# ADC.net
KiCad netlist of a schematic drawn in Altium Designer
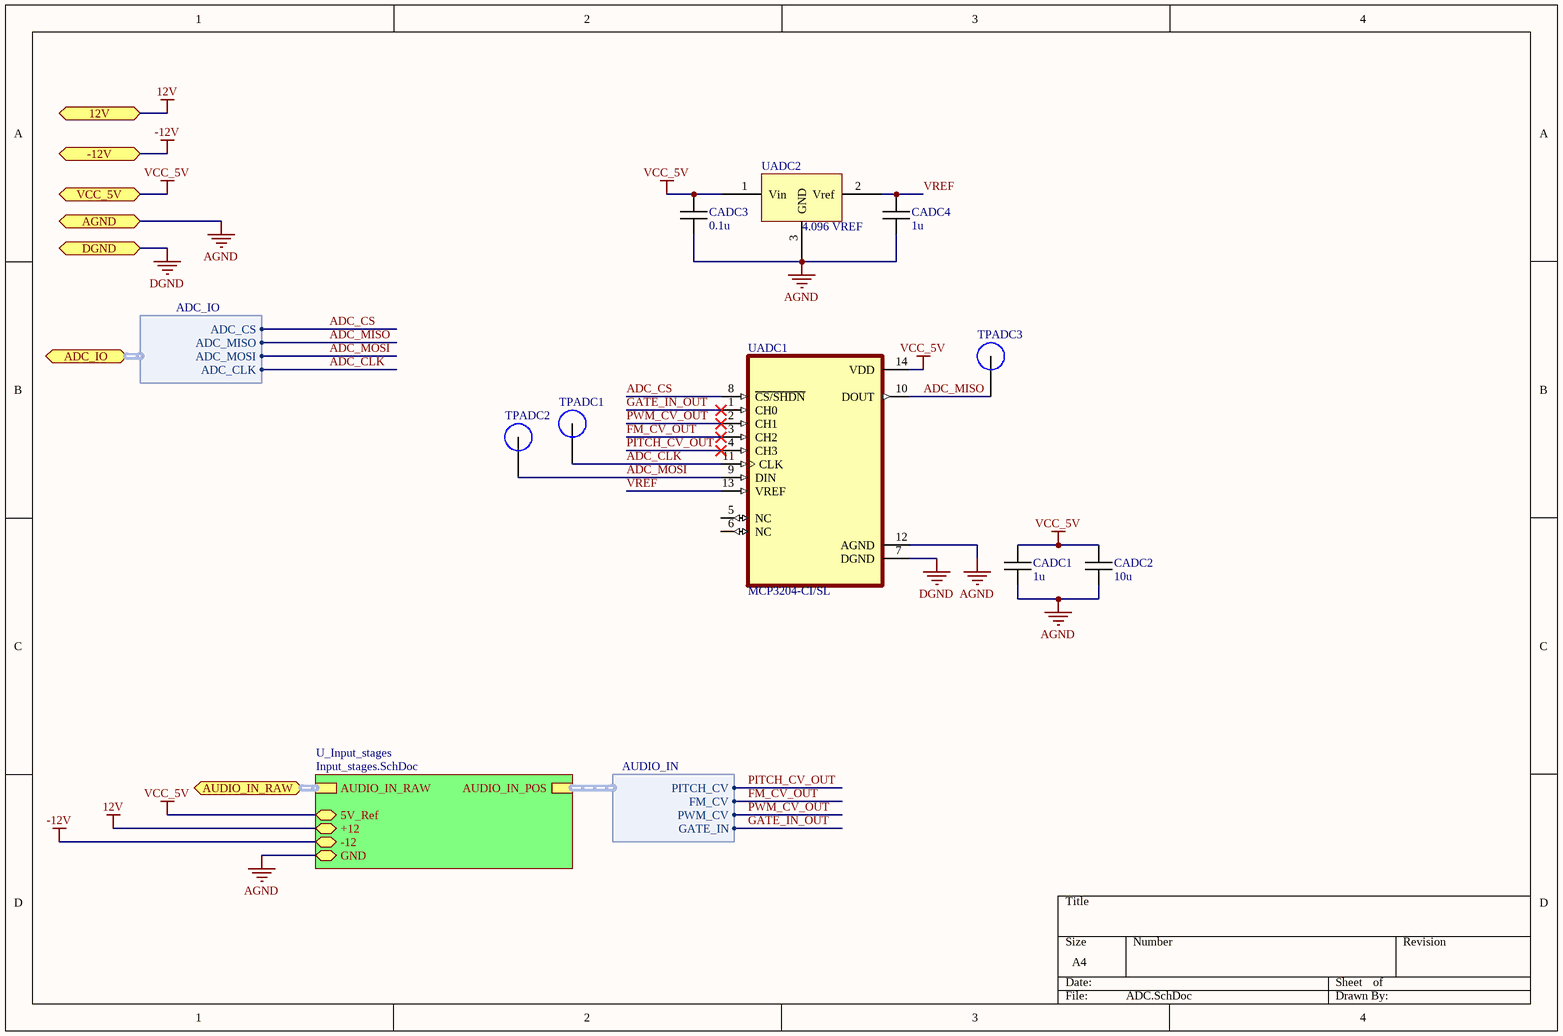
[diagram p0: ADC.SchDoc]

(export (version "E")
  (design (tool "Eeschema 10.0.6"))
  (components
    (comp (ref "CADC1")
      (value "1u")
      (footprint "C 0603 / 1608")
      (libsource (lib "Standard") (part "Capacitor"))
    )
    (comp (ref "CADC2")
      (value "10u")
      (footprint "C 0603 / 1608")
      (libsource (lib "Standard") (part "Capacitor"))
    )
    (comp (ref "CADC3")
      (value "0.1u")
      (footprint "C 0603 / 1608")
      (libsource (lib "Standard") (part "Capacitor"))
    )
    (comp (ref "CADC4")
      (value "1u")
      (footprint "C 0603 / 1608")
      (libsource (lib "Standard") (part "Capacitor"))
    )
    (comp (ref "TPADC1")
      (value "Test Point")
      (footprint "Test POint")
      (libsource (lib "Standard") (part "Test Point"))
    )
    (comp (ref "TPADC2")
      (value "Test Point")
      (footprint "Test POint")
      (libsource (lib "Standard") (part "Test Point"))
    )
    (comp (ref "TPADC3")
      (value "Test Point")
      (footprint "Test POint")
      (libsource (lib "Standard") (part "Test Point"))
    )
    (comp (ref "UADC1")
      (value "MCP3204-CI/SL")
      (footprint "SOIC-14")
      (description "12 Bit Analog to Digital Converter 2, 4 Input 1 SAR 14-SOIC")
      (fields (field (name "MF") "Microchip"))
      (libsource (lib "IC") (part "MCP3204-CI/SL"))
    )
    (comp (ref "UADC2")
      (value "4.096 VREF")
      (footprint "SOT-23-3")
      (description "4.096 Voltage reference")
      (libsource (lib "IC") (part "MCP1541"))
    )
  )
  (nets
    (net (code "5") (name "/ADC_CLK") (class "Default")
      (node (ref "TPADC1") (pin "1") (pintype "passive"))
      (node (ref "UADC1") (pin "11") (pinfunction "CLK_11") (pintype "input"))
    )
    (net (code "6") (name "/ADC_CS") (class "Default")
      (node (ref "UADC1") (pin "8") (pinfunction "~{CS/SHDN}_8") (pintype "input"))
    )
    (net (code "7") (name "/ADC_MISO") (class "Default")
      (node (ref "TPADC3") (pin "1") (pintype "passive"))
      (node (ref "UADC1") (pin "10") (pinfunction "DOUT_10") (pintype "output"))
    )
    (net (code "8") (name "/ADC_MOSI") (class "Default")
      (node (ref "TPADC2") (pin "1") (pintype "passive"))
      (node (ref "UADC1") (pin "9") (pinfunction "DIN_9") (pintype "input"))
    )
    (net (code "10") (name "/FM_CV_OUT") (class "Default")
      (node (ref "UADC1") (pin "3") (pinfunction "CH2_3") (pintype "input"))
    )
    (net (code "11") (name "/GATE_IN_OUT") (class "Default")
      (node (ref "UADC1") (pin "1") (pinfunction "CH0_1") (pintype "input"))
    )
    (net (code "12") (name "/PITCH_CV_OUT") (class "Default")
      (node (ref "UADC1") (pin "4") (pinfunction "CH3_4") (pintype "input"))
    )
    (net (code "13") (name "/PWM_CV_OUT") (class "Default")
      (node (ref "UADC1") (pin "2") (pinfunction "CH1_2") (pintype "input"))
    )
    (net (code "14") (name "/VREF") (class "Default")
      (node (ref "CADC4") (pin "1") (pinfunction "1_1") (pintype "passive"))
      (node (ref "UADC1") (pin "13") (pinfunction "VREF_13") (pintype "input"))
      (node (ref "UADC2") (pin "2") (pinfunction "Vref_2") (pintype "passive"))
    )
    (net (code "18") (name "AGND") (class "Default")
      (node (ref "CADC1") (pin "2") (pinfunction "1_2") (pintype "passive"))
      (node (ref "CADC2") (pin "2") (pinfunction "1_2") (pintype "passive"))
      (node (ref "CADC3") (pin "2") (pinfunction "1_2") (pintype "passive"))
      (node (ref "CADC4") (pin "2") (pinfunction "1_2") (pintype "passive"))
      (node (ref "UADC1") (pin "12") (pinfunction "AGND_12") (pintype "power_in"))
      (node (ref "UADC2") (pin "3") (pinfunction "GND_3") (pintype "passive"))
    )
    (net (code "19") (name "DGND") (class "Default")
      (node (ref "UADC1") (pin "7") (pinfunction "DGND_7") (pintype "power_in"))
    )
    (net (code "20") (name "VCC_5V") (class "Default")
      (node (ref "CADC1") (pin "1") (pinfunction "1_1") (pintype "passive"))
      (node (ref "CADC2") (pin "1") (pinfunction "1_1") (pintype "passive"))
      (node (ref "CADC3") (pin "1") (pinfunction "1_1") (pintype "passive"))
      (node (ref "UADC1") (pin "14") (pinfunction "VDD_14") (pintype "power_in"))
      (node (ref "UADC2") (pin "1") (pinfunction "Vin_1") (pintype "passive"))
    )
    (net (code "21") (name "unconnected-(UADC1-NC-Pad5)") (class "Default")
      (node (ref "UADC1") (pin "5") (pinfunction "NC_5") (pintype "bidirectional"))
    )
    (net (code "22") (name "unconnected-(UADC1-NC-Pad6)") (class "Default")
      (node (ref "UADC1") (pin "6") (pinfunction "NC_6") (pintype "bidirectional"))
    )
  )
)
